# flute.net
KiCad netlist of a schematic drawn in EAGLE
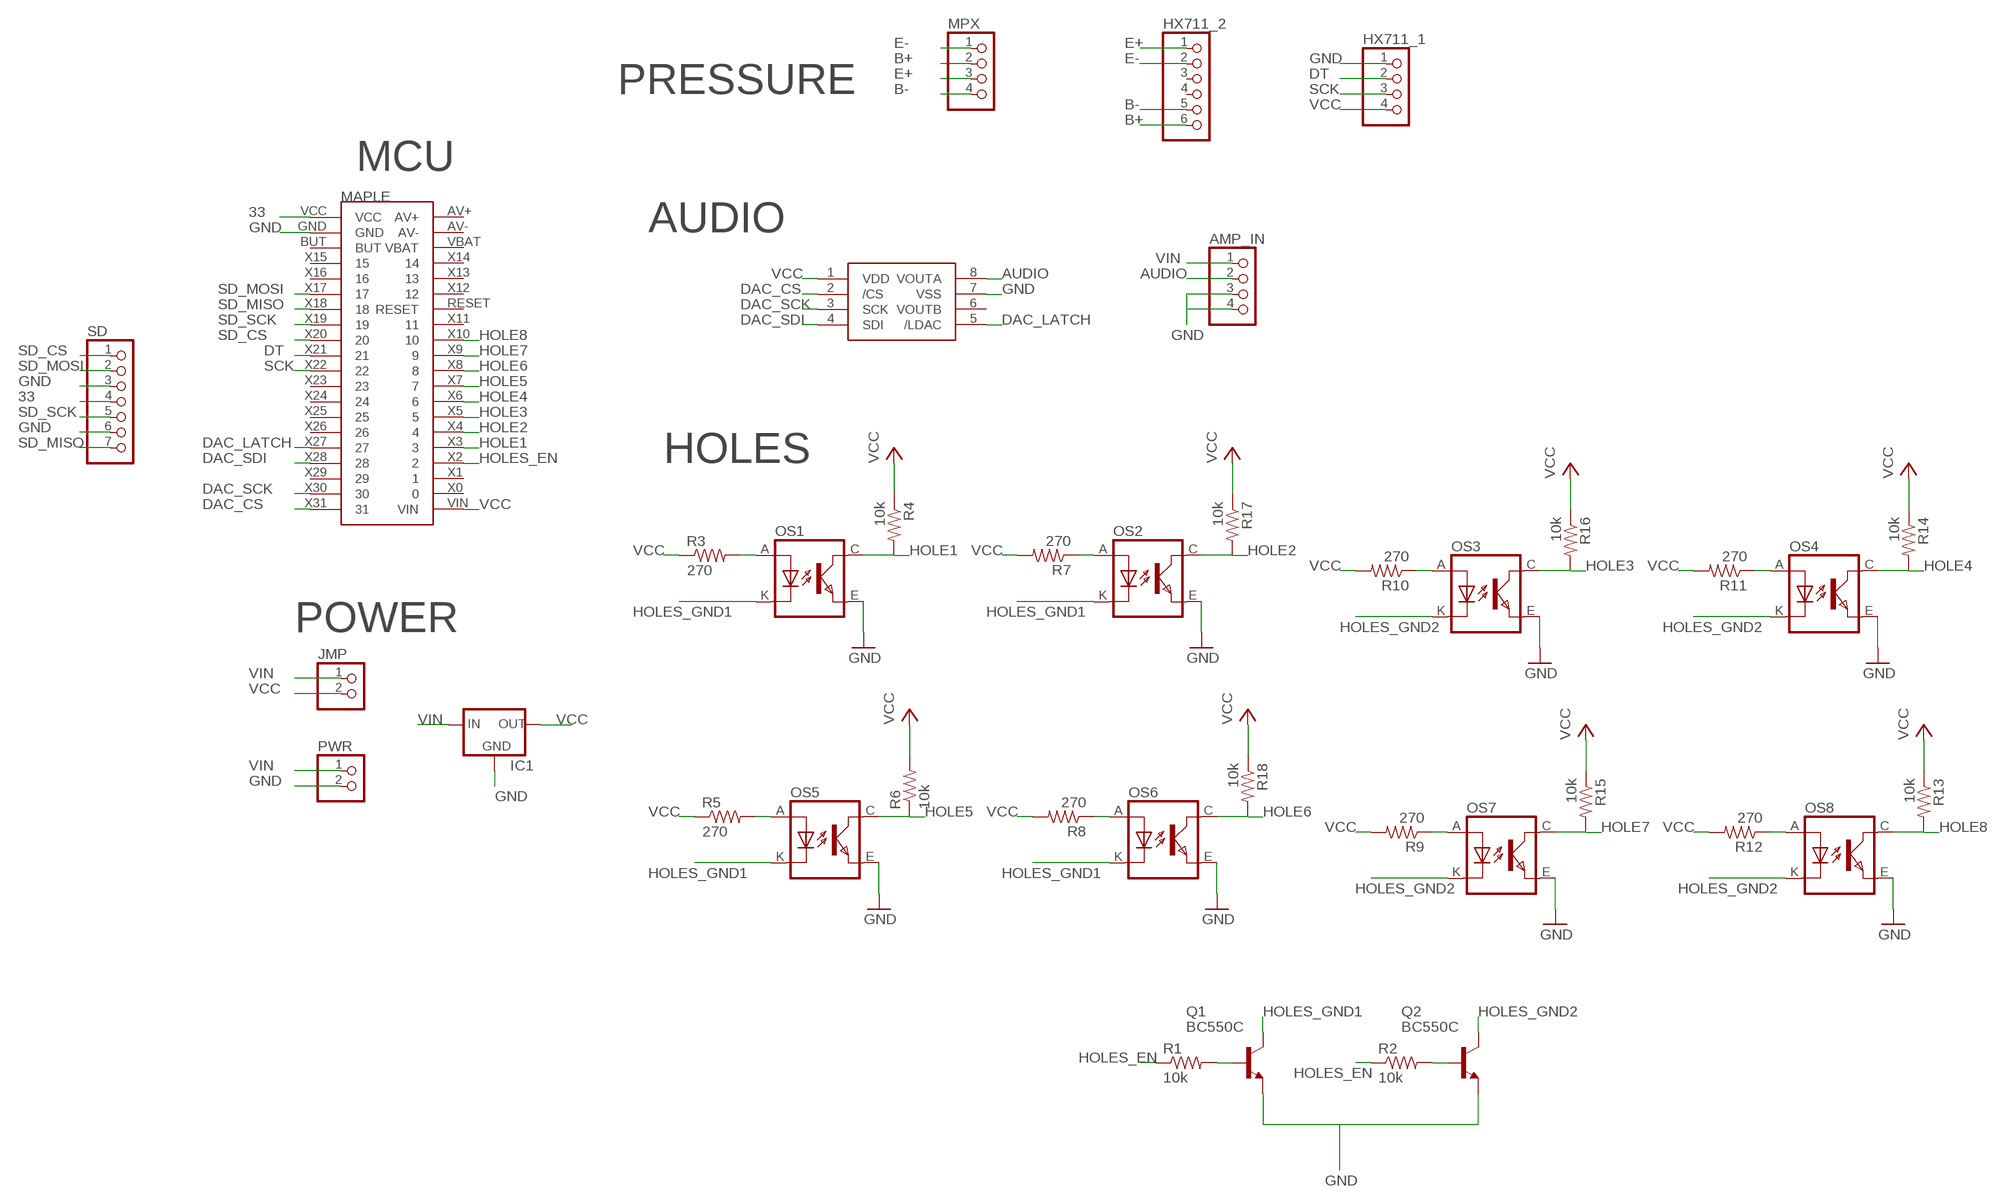
[diagram p0: schematic, sheet 1]

(export (version "E")
  (design (tool "Eeschema 10.0.6"))
  (components
    (comp (ref "AMP_IN")
      (value "CONNEC_1X04")
      (footprint "eagle-import:CONNEC_1X04")
      (libsource (lib "eagle-import") (part "CONNEC_1X04"))
    )
    (comp (ref "HX711_1")
      (value "CONNEC_1X04")
      (footprint "eagle-import:CONNEC_1X04")
      (libsource (lib "eagle-import") (part "CONNEC_1X04"))
    )
    (comp (ref "HX711_2")
      (value "CONNEC_1X06")
      (footprint "eagle-import:CONNEC_1X06")
      (libsource (lib "eagle-import") (part "CONNEC_1X06"))
    )
    (comp (ref "IC1")
      (value "V_REG_78XX-TO-220")
      (footprint "eagle-import:TO-220-ALT")
      (libsource (lib "eagle-import") (part "V_REG_78XX-TO-220"))
    )
    (comp (ref "JMP")
      (value "CONNEC_1X02BASIC")
      (footprint "eagle-import:CONNEC_1X02")
      (libsource (lib "eagle-import") (part "CONNEC_1X02BASIC"))
    )
    (comp (ref "MAPLE")
      (value "MAPLE_MINI")
      (footprint "eagle-import:CONNEC_2X20")
      (libsource (lib "eagle-import") (part "MAPLE_MINI"))
    )
    (comp (ref "MPX")
      (value "CONNEC_1X04")
      (footprint "eagle-import:CONNEC_1X04")
      (libsource (lib "eagle-import") (part "CONNEC_1X04"))
    )
    (comp (ref "OS1")
      (value "TCRT5000")
      (footprint "eagle-import:TCRT5000")
      (libsource (lib "eagle-import") (part "TCRT5000"))
    )
    (comp (ref "OS2")
      (value "TCRT5000")
      (footprint "eagle-import:TCRT5000")
      (libsource (lib "eagle-import") (part "TCRT5000"))
    )
    (comp (ref "OS3")
      (value "TCRT5000")
      (footprint "eagle-import:TCRT5000")
      (libsource (lib "eagle-import") (part "TCRT5000"))
    )
    (comp (ref "OS4")
      (value "TCRT5000")
      (footprint "eagle-import:TCRT5000")
      (libsource (lib "eagle-import") (part "TCRT5000"))
    )
    (comp (ref "OS5")
      (value "TCRT5000")
      (footprint "eagle-import:TCRT5000")
      (libsource (lib "eagle-import") (part "TCRT5000"))
    )
    (comp (ref "OS6")
      (value "TCRT5000")
      (footprint "eagle-import:TCRT5000")
      (libsource (lib "eagle-import") (part "TCRT5000"))
    )
    (comp (ref "OS7")
      (value "TCRT5000")
      (footprint "eagle-import:TCRT5000")
      (libsource (lib "eagle-import") (part "TCRT5000"))
    )
    (comp (ref "OS8")
      (value "TCRT5000")
      (footprint "eagle-import:TCRT5000")
      (libsource (lib "eagle-import") (part "TCRT5000"))
    )
    (comp (ref "PWR")
      (value "CONNEC_1X02BASIC")
      (footprint "eagle-import:CONNEC_1X02")
      (libsource (lib "eagle-import") (part "CONNEC_1X02BASIC"))
    )
    (comp (ref "Q1")
      (value "BC550C")
      (footprint "eagle-import:TO92-EBC")
      (libsource (lib "eagle-import") (part "BC550C"))
    )
    (comp (ref "Q2")
      (value "BC550C")
      (footprint "eagle-import:TO92-EBC")
      (libsource (lib "eagle-import") (part "BC550C"))
    )
    (comp (ref "R1")
      (value "10k")
      (footprint "eagle-import:0805")
      (libsource (lib "eagle-import") (part "RESISTOR0805-RES"))
    )
    (comp (ref "R2")
      (value "10k")
      (footprint "eagle-import:0805")
      (libsource (lib "eagle-import") (part "RESISTOR0805-RES"))
    )
    (comp (ref "R3")
      (value "270")
      (footprint "eagle-import:0805")
      (libsource (lib "eagle-import") (part "RESISTOR0805-RES"))
    )
    (comp (ref "R4")
      (value "10k")
      (footprint "eagle-import:0805")
      (libsource (lib "eagle-import") (part "RESISTOR0805-RES"))
    )
    (comp (ref "R5")
      (value "270")
      (footprint "eagle-import:0805")
      (libsource (lib "eagle-import") (part "RESISTOR0805-RES"))
    )
    (comp (ref "R6")
      (value "10k")
      (footprint "eagle-import:0805")
      (libsource (lib "eagle-import") (part "RESISTOR0805-RES"))
    )
    (comp (ref "R7")
      (value "270")
      (footprint "eagle-import:0805")
      (libsource (lib "eagle-import") (part "RESISTOR0805-RES"))
    )
    (comp (ref "R8")
      (value "270")
      (footprint "eagle-import:0805")
      (libsource (lib "eagle-import") (part "RESISTOR0805-RES"))
    )
    (comp (ref "R9")
      (value "270")
      (footprint "eagle-import:0805")
      (libsource (lib "eagle-import") (part "RESISTOR0805-RES"))
    )
    (comp (ref "R10")
      (value "270")
      (footprint "eagle-import:0805")
      (libsource (lib "eagle-import") (part "RESISTOR0805-RES"))
    )
    (comp (ref "R11")
      (value "270")
      (footprint "eagle-import:0805")
      (libsource (lib "eagle-import") (part "RESISTOR0805-RES"))
    )
    (comp (ref "R12")
      (value "270")
      (footprint "eagle-import:0805")
      (libsource (lib "eagle-import") (part "RESISTOR0805-RES"))
    )
    (comp (ref "R13")
      (value "10k")
      (footprint "eagle-import:0805")
      (libsource (lib "eagle-import") (part "RESISTOR0805-RES"))
    )
    (comp (ref "R14")
      (value "10k")
      (footprint "eagle-import:0805")
      (libsource (lib "eagle-import") (part "RESISTOR0805-RES"))
    )
    (comp (ref "R15")
      (value "10k")
      (footprint "eagle-import:0805")
      (libsource (lib "eagle-import") (part "RESISTOR0805-RES"))
    )
    (comp (ref "R16")
      (value "10k")
      (footprint "eagle-import:0805")
      (libsource (lib "eagle-import") (part "RESISTOR0805-RES"))
    )
    (comp (ref "R17")
      (value "10k")
      (footprint "eagle-import:0805")
      (libsource (lib "eagle-import") (part "RESISTOR0805-RES"))
    )
    (comp (ref "R18")
      (value "10k")
      (footprint "eagle-import:0805")
      (libsource (lib "eagle-import") (part "RESISTOR0805-RES"))
    )
    (comp (ref "SD")
      (value "CONNEC_1X07")
      (footprint "eagle-import:CONNEC_1X07")
      (libsource (lib "eagle-import") (part "CONNEC_1X07"))
    )
    (comp (ref "U$17")
      (value "MCP4822")
      (footprint "eagle-import:SO08")
      (libsource (lib "eagle-import") (part "MCP4822"))
    )
  )
  (nets
    (net (code "1") (name "/33") (class "Default")
      (node (ref "MAPLE") (pin "VCC") (pinfunction "VCC_VCC") (pintype "bidirectional"))
      (node (ref "SD") (pin "4") (pinfunction "4_4") (pintype "passive"))
    )
    (net (code "2") (name "/AUDIO") (class "Default")
      (node (ref "AMP_IN") (pin "2") (pinfunction "2_2") (pintype "passive"))
      (node (ref "U$17") (pin "8") (pinfunction "VOUTA_8") (pintype "bidirectional"))
    )
    (net (code "3") (name "/B+") (class "Default")
      (node (ref "HX711_2") (pin "6") (pinfunction "6_6") (pintype "passive"))
      (node (ref "MPX") (pin "2") (pinfunction "2_2") (pintype "passive"))
    )
    (net (code "4") (name "/B-") (class "Default")
      (node (ref "HX711_2") (pin "5") (pinfunction "5_5") (pintype "passive"))
      (node (ref "MPX") (pin "4") (pinfunction "4_4") (pintype "passive"))
    )
    (net (code "5") (name "/DAC_CS") (class "Default")
      (node (ref "MAPLE") (pin "X31") (pinfunction "31_X31") (pintype "bidirectional"))
      (node (ref "U$17") (pin "2") (pinfunction "/CS_2") (pintype "bidirectional"))
    )
    (net (code "6") (name "/DAC_LATCH") (class "Default")
      (node (ref "MAPLE") (pin "X27") (pinfunction "27_X27") (pintype "bidirectional"))
      (node (ref "U$17") (pin "5") (pinfunction "/LDAC_5") (pintype "bidirectional"))
    )
    (net (code "7") (name "/DAC_SCK") (class "Default")
      (node (ref "MAPLE") (pin "X30") (pinfunction "30_X30") (pintype "bidirectional"))
      (node (ref "U$17") (pin "3") (pinfunction "SCK_3") (pintype "bidirectional"))
    )
    (net (code "8") (name "/DAC_SDI") (class "Default")
      (node (ref "MAPLE") (pin "X28") (pinfunction "28_X28") (pintype "bidirectional"))
      (node (ref "U$17") (pin "4") (pinfunction "SDI_4") (pintype "bidirectional"))
    )
    (net (code "9") (name "/DT") (class "Default")
      (node (ref "HX711_1") (pin "2") (pinfunction "2_2") (pintype "passive"))
      (node (ref "MAPLE") (pin "X21") (pinfunction "21_X21") (pintype "bidirectional"))
    )
    (net (code "10") (name "/E+") (class "Default")
      (node (ref "HX711_2") (pin "1") (pinfunction "1_1") (pintype "passive"))
      (node (ref "MPX") (pin "3") (pinfunction "3_3") (pintype "passive"))
    )
    (net (code "11") (name "/E-") (class "Default")
      (node (ref "HX711_2") (pin "2") (pinfunction "2_2") (pintype "passive"))
      (node (ref "MPX") (pin "1") (pinfunction "1_1") (pintype "passive"))
    )
    (net (code "12") (name "/HOLE1") (class "Default")
      (node (ref "MAPLE") (pin "X3") (pinfunction "3_X3") (pintype "bidirectional"))
      (node (ref "OS1") (pin "C") (pinfunction "COLLECTOR_C") (pintype "passive"))
      (node (ref "R4") (pin "2") (pinfunction "2_2") (pintype "passive"))
    )
    (net (code "13") (name "/HOLE2") (class "Default")
      (node (ref "MAPLE") (pin "X4") (pinfunction "4_X4") (pintype "bidirectional"))
      (node (ref "OS2") (pin "C") (pinfunction "COLLECTOR_C") (pintype "passive"))
      (node (ref "R17") (pin "2") (pinfunction "2_2") (pintype "passive"))
    )
    (net (code "14") (name "/HOLE3") (class "Default")
      (node (ref "MAPLE") (pin "X5") (pinfunction "5_X5") (pintype "bidirectional"))
      (node (ref "OS3") (pin "C") (pinfunction "COLLECTOR_C") (pintype "passive"))
      (node (ref "R16") (pin "2") (pinfunction "2_2") (pintype "passive"))
    )
    (net (code "15") (name "/HOLE4") (class "Default")
      (node (ref "MAPLE") (pin "X6") (pinfunction "6_X6") (pintype "bidirectional"))
      (node (ref "OS4") (pin "C") (pinfunction "COLLECTOR_C") (pintype "passive"))
      (node (ref "R14") (pin "2") (pinfunction "2_2") (pintype "passive"))
    )
    (net (code "16") (name "/HOLE5") (class "Default")
      (node (ref "MAPLE") (pin "X7") (pinfunction "7_X7") (pintype "bidirectional"))
      (node (ref "OS5") (pin "C") (pinfunction "COLLECTOR_C") (pintype "passive"))
      (node (ref "R6") (pin "1") (pinfunction "1_1") (pintype "passive"))
    )
    (net (code "17") (name "/HOLE6") (class "Default")
      (node (ref "MAPLE") (pin "X8") (pinfunction "8_X8") (pintype "bidirectional"))
      (node (ref "OS6") (pin "C") (pinfunction "COLLECTOR_C") (pintype "passive"))
      (node (ref "R18") (pin "2") (pinfunction "2_2") (pintype "passive"))
    )
    (net (code "18") (name "/HOLE7") (class "Default")
      (node (ref "MAPLE") (pin "X9") (pinfunction "9_X9") (pintype "bidirectional"))
      (node (ref "OS7") (pin "C") (pinfunction "COLLECTOR_C") (pintype "passive"))
      (node (ref "R15") (pin "2") (pinfunction "2_2") (pintype "passive"))
    )
    (net (code "19") (name "/HOLE8") (class "Default")
      (node (ref "MAPLE") (pin "X10") (pinfunction "10_X10") (pintype "bidirectional"))
      (node (ref "OS8") (pin "C") (pinfunction "COLLECTOR_C") (pintype "passive"))
      (node (ref "R13") (pin "2") (pinfunction "2_2") (pintype "passive"))
    )
    (net (code "20") (name "/HOLES_EN") (class "Default")
      (node (ref "MAPLE") (pin "X2") (pinfunction "2_X2") (pintype "bidirectional"))
      (node (ref "R1") (pin "1") (pinfunction "1_1") (pintype "passive"))
      (node (ref "R2") (pin "1") (pinfunction "1_1") (pintype "passive"))
    )
    (net (code "21") (name "/HOLES_GND1") (class "Default")
      (node (ref "OS1") (pin "K") (pinfunction "CATHODE_K") (pintype "passive"))
      (node (ref "OS2") (pin "K") (pinfunction "CATHODE_K") (pintype "passive"))
      (node (ref "OS5") (pin "K") (pinfunction "CATHODE_K") (pintype "passive"))
      (node (ref "OS6") (pin "K") (pinfunction "CATHODE_K") (pintype "passive"))
      (node (ref "Q1") (pin "C") (pinfunction "C_C") (pintype "passive"))
    )
    (net (code "22") (name "/HOLES_GND2") (class "Default")
      (node (ref "OS3") (pin "K") (pinfunction "CATHODE_K") (pintype "passive"))
      (node (ref "OS4") (pin "K") (pinfunction "CATHODE_K") (pintype "passive"))
      (node (ref "OS7") (pin "K") (pinfunction "CATHODE_K") (pintype "passive"))
      (node (ref "OS8") (pin "K") (pinfunction "CATHODE_K") (pintype "passive"))
      (node (ref "Q2") (pin "C") (pinfunction "C_C") (pintype "passive"))
    )
    (net (code "23") (name "/SCK") (class "Default")
      (node (ref "HX711_1") (pin "3") (pinfunction "3_3") (pintype "passive"))
      (node (ref "MAPLE") (pin "X22") (pinfunction "22_X22") (pintype "bidirectional"))
    )
    (net (code "24") (name "/SD_CS") (class "Default")
      (node (ref "MAPLE") (pin "X20") (pinfunction "20_X20") (pintype "bidirectional"))
      (node (ref "SD") (pin "1") (pinfunction "1_1") (pintype "passive"))
    )
    (net (code "25") (name "/SD_MISO") (class "Default")
      (node (ref "MAPLE") (pin "X18") (pinfunction "18_X18") (pintype "bidirectional"))
      (node (ref "SD") (pin "7") (pinfunction "7_7") (pintype "passive"))
    )
    (net (code "26") (name "/SD_MOSI") (class "Default")
      (node (ref "MAPLE") (pin "X17") (pinfunction "17_X17") (pintype "bidirectional"))
      (node (ref "SD") (pin "2") (pinfunction "2_2") (pintype "passive"))
    )
    (net (code "27") (name "/SD_SCK") (class "Default")
      (node (ref "MAPLE") (pin "X19") (pinfunction "19_X19") (pintype "bidirectional"))
      (node (ref "SD") (pin "5") (pinfunction "5_5") (pintype "passive"))
    )
    (net (code "28") (name "/VIN") (class "Default")
      (node (ref "AMP_IN") (pin "1") (pinfunction "1_1") (pintype "passive"))
      (node (ref "IC1") (pin "IN") (pinfunction "IN_IN") (pintype "input"))
      (node (ref "JMP") (pin "1") (pinfunction "1_1") (pintype "passive"))
      (node (ref "PWR") (pin "1") (pinfunction "1_1") (pintype "passive"))
    )
    (net (code "29") (name "GND") (class "Default")
      (node (ref "AMP_IN") (pin "3") (pinfunction "3_3") (pintype "passive"))
      (node (ref "AMP_IN") (pin "4") (pinfunction "4_4") (pintype "passive"))
      (node (ref "HX711_1") (pin "1") (pinfunction "1_1") (pintype "passive"))
      (node (ref "IC1") (pin "GND") (pinfunction "GND_GND") (pintype "input"))
      (node (ref "MAPLE") (pin "GND") (pinfunction "GND_GND") (pintype "bidirectional"))
      (node (ref "OS1") (pin "E") (pinfunction "EMITTER_E") (pintype "passive"))
      (node (ref "OS2") (pin "E") (pinfunction "EMITTER_E") (pintype "passive"))
      (node (ref "OS3") (pin "E") (pinfunction "EMITTER_E") (pintype "passive"))
      (node (ref "OS4") (pin "E") (pinfunction "EMITTER_E") (pintype "passive"))
      (node (ref "OS5") (pin "E") (pinfunction "EMITTER_E") (pintype "passive"))
      (node (ref "OS6") (pin "E") (pinfunction "EMITTER_E") (pintype "passive"))
      (node (ref "OS7") (pin "E") (pinfunction "EMITTER_E") (pintype "passive"))
      (node (ref "OS8") (pin "E") (pinfunction "EMITTER_E") (pintype "passive"))
      (node (ref "PWR") (pin "2") (pinfunction "2_2") (pintype "passive"))
      (node (ref "Q1") (pin "E") (pinfunction "E_E") (pintype "passive"))
      (node (ref "Q2") (pin "E") (pinfunction "E_E") (pintype "passive"))
      (node (ref "SD") (pin "3") (pinfunction "3_3") (pintype "passive"))
      (node (ref "SD") (pin "6") (pinfunction "6_6") (pintype "passive"))
      (node (ref "U$17") (pin "7") (pinfunction "VSS_7") (pintype "bidirectional"))
    )
    (net (code "30") (name "Net-(OS1-ANODE)") (class "Default")
      (node (ref "OS1") (pin "A") (pinfunction "ANODE_A") (pintype "passive"))
      (node (ref "R3") (pin "2") (pinfunction "2_2") (pintype "passive"))
    )
    (net (code "31") (name "Net-(OS2-ANODE)") (class "Default")
      (node (ref "OS2") (pin "A") (pinfunction "ANODE_A") (pintype "passive"))
      (node (ref "R7") (pin "1") (pinfunction "1_1") (pintype "passive"))
    )
    (net (code "32") (name "Net-(OS3-ANODE)") (class "Default")
      (node (ref "OS3") (pin "A") (pinfunction "ANODE_A") (pintype "passive"))
      (node (ref "R10") (pin "1") (pinfunction "1_1") (pintype "passive"))
    )
    (net (code "33") (name "Net-(OS4-ANODE)") (class "Default")
      (node (ref "OS4") (pin "A") (pinfunction "ANODE_A") (pintype "passive"))
      (node (ref "R11") (pin "1") (pinfunction "1_1") (pintype "passive"))
    )
    (net (code "34") (name "Net-(OS5-ANODE)") (class "Default")
      (node (ref "OS5") (pin "A") (pinfunction "ANODE_A") (pintype "passive"))
      (node (ref "R5") (pin "2") (pinfunction "2_2") (pintype "passive"))
    )
    (net (code "35") (name "Net-(OS6-ANODE)") (class "Default")
      (node (ref "OS6") (pin "A") (pinfunction "ANODE_A") (pintype "passive"))
      (node (ref "R8") (pin "1") (pinfunction "1_1") (pintype "passive"))
    )
    (net (code "36") (name "Net-(OS7-ANODE)") (class "Default")
      (node (ref "OS7") (pin "A") (pinfunction "ANODE_A") (pintype "passive"))
      (node (ref "R9") (pin "1") (pinfunction "1_1") (pintype "passive"))
    )
    (net (code "37") (name "Net-(OS8-ANODE)") (class "Default")
      (node (ref "OS8") (pin "A") (pinfunction "ANODE_A") (pintype "passive"))
      (node (ref "R12") (pin "1") (pinfunction "1_1") (pintype "passive"))
    )
    (net (code "38") (name "Net-(Q1-PadB)") (class "Default")
      (node (ref "Q1") (pin "B") (pinfunction "B_B") (pintype "passive"))
      (node (ref "R1") (pin "2") (pinfunction "2_2") (pintype "passive"))
    )
    (net (code "39") (name "Net-(Q2-PadB)") (class "Default")
      (node (ref "Q2") (pin "B") (pinfunction "B_B") (pintype "passive"))
      (node (ref "R2") (pin "2") (pinfunction "2_2") (pintype "passive"))
    )
    (net (code "40") (name "VCC") (class "Default")
      (node (ref "HX711_1") (pin "4") (pinfunction "4_4") (pintype "passive"))
      (node (ref "IC1") (pin "OUT") (pinfunction "OUT_OUT") (pintype "output"))
      (node (ref "JMP") (pin "2") (pinfunction "2_2") (pintype "passive"))
      (node (ref "MAPLE") (pin "VIN") (pinfunction "VIN_VIN") (pintype "bidirectional"))
      (node (ref "R10") (pin "2") (pinfunction "2_2") (pintype "passive"))
      (node (ref "R11") (pin "2") (pinfunction "2_2") (pintype "passive"))
      (node (ref "R12") (pin "2") (pinfunction "2_2") (pintype "passive"))
      (node (ref "R13") (pin "1") (pinfunction "1_1") (pintype "passive"))
      (node (ref "R14") (pin "1") (pinfunction "1_1") (pintype "passive"))
      (node (ref "R15") (pin "1") (pinfunction "1_1") (pintype "passive"))
      (node (ref "R16") (pin "1") (pinfunction "1_1") (pintype "passive"))
      (node (ref "R17") (pin "1") (pinfunction "1_1") (pintype "passive"))
      (node (ref "R18") (pin "1") (pinfunction "1_1") (pintype "passive"))
      (node (ref "R3") (pin "1") (pinfunction "1_1") (pintype "passive"))
      (node (ref "R4") (pin "1") (pinfunction "1_1") (pintype "passive"))
      (node (ref "R5") (pin "1") (pinfunction "1_1") (pintype "passive"))
      (node (ref "R6") (pin "2") (pinfunction "2_2") (pintype "passive"))
      (node (ref "R7") (pin "2") (pinfunction "2_2") (pintype "passive"))
      (node (ref "R8") (pin "2") (pinfunction "2_2") (pintype "passive"))
      (node (ref "R9") (pin "2") (pinfunction "2_2") (pintype "passive"))
      (node (ref "U$17") (pin "1") (pinfunction "VDD_1") (pintype "bidirectional"))
    )
    (net (code "41") (name "unconnected-(HX711_2-Pad3)") (class "Default")
      (node (ref "HX711_2") (pin "3") (pinfunction "3_3") (pintype "passive"))
    )
    (net (code "42") (name "unconnected-(HX711_2-Pad4)") (class "Default")
      (node (ref "HX711_2") (pin "4") (pinfunction "4_4") (pintype "passive"))
    )
    (net (code "43") (name "unconnected-(MAPLE-0-PadX0)") (class "Default")
      (node (ref "MAPLE") (pin "X0") (pinfunction "0_X0") (pintype "bidirectional"))
    )
    (net (code "44") (name "unconnected-(MAPLE-1-PadX1)") (class "Default")
      (node (ref "MAPLE") (pin "X1") (pinfunction "1_X1") (pintype "bidirectional"))
    )
    (net (code "45") (name "unconnected-(MAPLE-11-PadX11)") (class "Default")
      (node (ref "MAPLE") (pin "X11") (pinfunction "11_X11") (pintype "bidirectional"))
    )
    (net (code "46") (name "unconnected-(MAPLE-12-PadX12)") (class "Default")
      (node (ref "MAPLE") (pin "X12") (pinfunction "12_X12") (pintype "bidirectional"))
    )
    (net (code "47") (name "unconnected-(MAPLE-13-PadX13)") (class "Default")
      (node (ref "MAPLE") (pin "X13") (pinfunction "13_X13") (pintype "bidirectional"))
    )
    (net (code "48") (name "unconnected-(MAPLE-14-PadX14)") (class "Default")
      (node (ref "MAPLE") (pin "X14") (pinfunction "14_X14") (pintype "bidirectional"))
    )
    (net (code "49") (name "unconnected-(MAPLE-15-PadX15)") (class "Default")
      (node (ref "MAPLE") (pin "X15") (pinfunction "15_X15") (pintype "bidirectional"))
    )
    (net (code "50") (name "unconnected-(MAPLE-16-PadX16)") (class "Default")
      (node (ref "MAPLE") (pin "X16") (pinfunction "16_X16") (pintype "bidirectional"))
    )
    (net (code "51") (name "unconnected-(MAPLE-23-PadX23)") (class "Default")
      (node (ref "MAPLE") (pin "X23") (pinfunction "23_X23") (pintype "bidirectional"))
    )
    (net (code "52") (name "unconnected-(MAPLE-24-PadX24)") (class "Default")
      (node (ref "MAPLE") (pin "X24") (pinfunction "24_X24") (pintype "bidirectional"))
    )
    (net (code "53") (name "unconnected-(MAPLE-25-PadX25)") (class "Default")
      (node (ref "MAPLE") (pin "X25") (pinfunction "25_X25") (pintype "bidirectional"))
    )
    (net (code "54") (name "unconnected-(MAPLE-26-PadX26)") (class "Default")
      (node (ref "MAPLE") (pin "X26") (pinfunction "26_X26") (pintype "bidirectional"))
    )
    (net (code "55") (name "unconnected-(MAPLE-29-PadX29)") (class "Default")
      (node (ref "MAPLE") (pin "X29") (pinfunction "29_X29") (pintype "bidirectional"))
    )
    (net (code "56") (name "unconnected-(MAPLE-PadAV+)") (class "Default")
      (node (ref "MAPLE") (pin "AV+") (pinfunction "AV+_AV+") (pintype "bidirectional"))
    )
    (net (code "57") (name "unconnected-(MAPLE-PadAV-)") (class "Default")
      (node (ref "MAPLE") (pin "AV-") (pinfunction "AV-_AV-") (pintype "bidirectional"))
    )
    (net (code "58") (name "unconnected-(MAPLE-PadBUT)") (class "Default")
      (node (ref "MAPLE") (pin "BUT") (pinfunction "BUT_BUT") (pintype "bidirectional"))
    )
    (net (code "59") (name "unconnected-(MAPLE-PadRESET)") (class "Default")
      (node (ref "MAPLE") (pin "RESET") (pinfunction "RESET_RESET") (pintype "bidirectional"))
    )
    (net (code "60") (name "unconnected-(MAPLE-PadVBAT)") (class "Default")
      (node (ref "MAPLE") (pin "VBAT") (pinfunction "VBAT_VBAT") (pintype "bidirectional"))
    )
    (net (code "61") (name "unconnected-(U$17-VOUTB-Pad6)") (class "Default")
      (node (ref "U$17") (pin "6") (pinfunction "VOUTB_6") (pintype "bidirectional"))
    )
  )
)
